# 2.net
KiCad netlist of a schematic drawn in Altium Designer
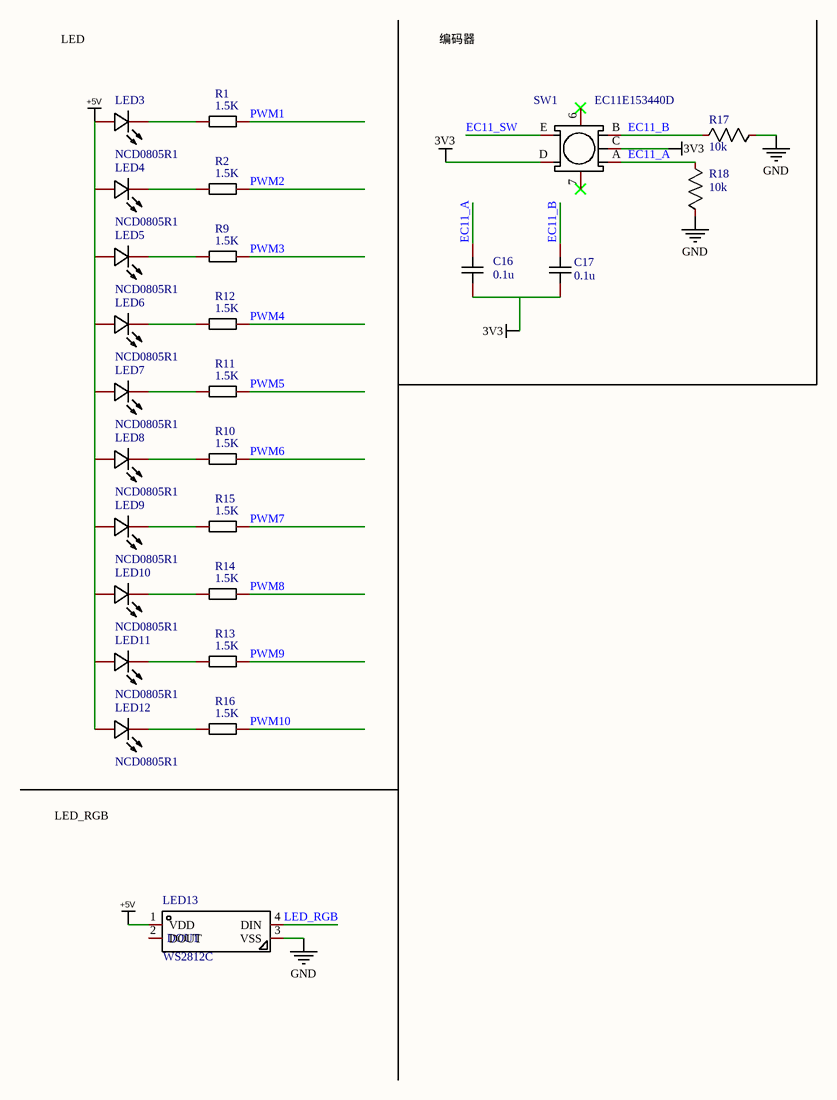
[diagram p0: 2_外围电路.schdoc]

(export (version "E")
  (design (tool "Eeschema 10.0.6"))
  (components
    (comp (ref "C16")
      (value "0.1u")
      (fields (field (name "NAME") "0.1u"))
      (libsource (lib "altium-import") (part "root_1_0.1u_"))
    )
    (comp (ref "C17")
      (value "0.1u")
      (fields (field (name "NAME") "0.1u"))
      (libsource (lib "altium-import") (part "root_1_0.1u_"))
    )
    (comp (ref "LED3")
      (value "NCD0805R1")
      (description "发光颜色:红灯;")
      (fields (field (name "NAME") "NCD0805R1") (field (name "MANUFACTURER") "国星光电"))
      (libsource (lib "altium-import") (part "root_2_NCD0805R1_"))
    )
    (comp (ref "LED4")
      (value "NCD0805R1")
      (description "发光颜色:红灯;")
      (fields (field (name "NAME") "NCD0805R1") (field (name "MANUFACTURER") "国星光电"))
      (libsource (lib "altium-import") (part "root_2_NCD0805R1_"))
    )
    (comp (ref "LED5")
      (value "NCD0805R1")
      (description "发光颜色:红灯;")
      (fields (field (name "NAME") "NCD0805R1") (field (name "MANUFACTURER") "国星光电"))
      (libsource (lib "altium-import") (part "root_2_NCD0805R1_"))
    )
    (comp (ref "LED6")
      (value "NCD0805R1")
      (description "发光颜色:红灯;")
      (fields (field (name "NAME") "NCD0805R1") (field (name "MANUFACTURER") "国星光电"))
      (libsource (lib "altium-import") (part "root_2_NCD0805R1_"))
    )
    (comp (ref "LED7")
      (value "NCD0805R1")
      (description "发光颜色:红灯;")
      (fields (field (name "NAME") "NCD0805R1") (field (name "MANUFACTURER") "国星光电"))
      (libsource (lib "altium-import") (part "root_2_NCD0805R1_"))
    )
    (comp (ref "LED8")
      (value "NCD0805R1")
      (description "发光颜色:红灯;")
      (fields (field (name "NAME") "NCD0805R1") (field (name "MANUFACTURER") "国星光电"))
      (libsource (lib "altium-import") (part "root_2_NCD0805R1_"))
    )
    (comp (ref "LED9")
      (value "NCD0805R1")
      (description "发光颜色:红灯;")
      (fields (field (name "NAME") "NCD0805R1") (field (name "MANUFACTURER") "国星光电"))
      (libsource (lib "altium-import") (part "root_2_NCD0805R1_"))
    )
    (comp (ref "LED10")
      (value "NCD0805R1")
      (description "发光颜色:红灯;")
      (fields (field (name "NAME") "NCD0805R1") (field (name "MANUFACTURER") "国星光电"))
      (libsource (lib "altium-import") (part "root_2_NCD0805R1_"))
    )
    (comp (ref "LED11")
      (value "NCD0805R1")
      (description "发光颜色:红灯;")
      (fields (field (name "NAME") "NCD0805R1") (field (name "MANUFACTURER") "国星光电"))
      (libsource (lib "altium-import") (part "root_2_NCD0805R1_"))
    )
    (comp (ref "LED12")
      (value "NCD0805R1")
      (description "发光颜色:红灯;")
      (fields (field (name "NAME") "NCD0805R1") (field (name "MANUFACTURER") "国星光电"))
      (libsource (lib "altium-import") (part "root_2_NCD0805R1_"))
    )
    (comp (ref "LED13")
      (value "WS2812C")
      (description "发光颜色:RGB三色;")
      (fields
        (field (name "NAME") "WS2812C")
        (field (name "MANUFACTURER") "worldsemi")
        (field (name "NAME_1") "DOUT")
      )
      (libsource (lib "altium-import") (part "root_0_WS2812C_"))
    )
    (comp (ref "R1")
      (value "1.5K")
      (fields
        (field (name "NAME") "1.5K")
        (field (name "MANUFACTURER") "YAGEO(国巨)")
        (field (name "MANUFACTURER PART") "AC0805FR-071K5L")
      )
      (libsource (lib "altium-import") (part "root_0_AC0805FR-071K5L_"))
    )
    (comp (ref "R2")
      (value "1.5K")
      (fields
        (field (name "NAME") "1.5K")
        (field (name "MANUFACTURER") "YAGEO(国巨)")
        (field (name "MANUFACTURER PART") "AC0805FR-071K5L")
      )
      (libsource (lib "altium-import") (part "root_0_AC0805FR-071K5L_"))
    )
    (comp (ref "R9")
      (value "1.5K")
      (fields
        (field (name "NAME") "1.5K")
        (field (name "MANUFACTURER") "YAGEO(国巨)")
        (field (name "MANUFACTURER PART") "AC0805FR-071K5L")
      )
      (libsource (lib "altium-import") (part "root_0_AC0805FR-071K5L_"))
    )
    (comp (ref "R10")
      (value "1.5K")
      (fields
        (field (name "NAME") "1.5K")
        (field (name "MANUFACTURER") "YAGEO(国巨)")
        (field (name "MANUFACTURER PART") "AC0805FR-071K5L")
      )
      (libsource (lib "altium-import") (part "root_0_AC0805FR-071K5L_"))
    )
    (comp (ref "R11")
      (value "1.5K")
      (fields
        (field (name "NAME") "1.5K")
        (field (name "MANUFACTURER") "YAGEO(国巨)")
        (field (name "MANUFACTURER PART") "AC0805FR-071K5L")
      )
      (libsource (lib "altium-import") (part "root_0_AC0805FR-071K5L_"))
    )
    (comp (ref "R12")
      (value "1.5K")
      (fields
        (field (name "NAME") "1.5K")
        (field (name "MANUFACTURER") "YAGEO(国巨)")
        (field (name "MANUFACTURER PART") "AC0805FR-071K5L")
      )
      (libsource (lib "altium-import") (part "root_0_AC0805FR-071K5L_"))
    )
    (comp (ref "R13")
      (value "1.5K")
      (fields
        (field (name "NAME") "1.5K")
        (field (name "MANUFACTURER") "YAGEO(国巨)")
        (field (name "MANUFACTURER PART") "AC0805FR-071K5L")
      )
      (libsource (lib "altium-import") (part "root_0_AC0805FR-071K5L_"))
    )
    (comp (ref "R14")
      (value "1.5K")
      (fields
        (field (name "NAME") "1.5K")
        (field (name "MANUFACTURER") "YAGEO(国巨)")
        (field (name "MANUFACTURER PART") "AC0805FR-071K5L")
      )
      (libsource (lib "altium-import") (part "root_0_AC0805FR-071K5L_"))
    )
    (comp (ref "R15")
      (value "1.5K")
      (fields
        (field (name "NAME") "1.5K")
        (field (name "MANUFACTURER") "YAGEO(国巨)")
        (field (name "MANUFACTURER PART") "AC0805FR-071K5L")
      )
      (libsource (lib "altium-import") (part "root_0_AC0805FR-071K5L_"))
    )
    (comp (ref "R16")
      (value "1.5K")
      (fields
        (field (name "NAME") "1.5K")
        (field (name "MANUFACTURER") "YAGEO(国巨)")
        (field (name "MANUFACTURER PART") "AC0805FR-071K5L")
      )
      (libsource (lib "altium-import") (part "root_0_AC0805FR-071K5L_"))
    )
    (comp (ref "R17")
      (value "10k")
      (fields (field (name "NAME") "10k"))
      (libsource (lib "altium-import") (part "root_2_10k_"))
    )
    (comp (ref "R18")
      (value "10k")
      (fields (field (name "NAME") "10k"))
      (libsource (lib "altium-import") (part "root_3_10k_"))
    )
    (comp (ref "SW1")
      (value "EC11E153440D")
      (fields (field (name "NAME") "EC11E153440D") (field (name "MANUFACTURER") "ALPSALPINE(阿尔卑斯阿尔派)"))
      (libsource (lib "altium-import") (part "root_1_EC11E153440D_"))
    )
  )
  (nets
    (net (code "1") (name "+5V") (class "Default")
      (node (ref "LED10") (pin "2") (pinfunction "+_2") (pintype "passive"))
      (node (ref "LED11") (pin "2") (pinfunction "+_2") (pintype "passive"))
      (node (ref "LED12") (pin "2") (pinfunction "+_2") (pintype "passive"))
      (node (ref "LED13") (pin "1") (pinfunction "VDD_1") (pintype "passive"))
      (node (ref "LED3") (pin "2") (pinfunction "+_2") (pintype "passive"))
      (node (ref "LED4") (pin "2") (pinfunction "+_2") (pintype "passive"))
      (node (ref "LED5") (pin "2") (pinfunction "+_2") (pintype "passive"))
      (node (ref "LED6") (pin "2") (pinfunction "+_2") (pintype "passive"))
      (node (ref "LED7") (pin "2") (pinfunction "+_2") (pintype "passive"))
      (node (ref "LED8") (pin "2") (pinfunction "+_2") (pintype "passive"))
      (node (ref "LED9") (pin "2") (pinfunction "+_2") (pintype "passive"))
    )
    (net (code "2") (name "/EC11_A") (class "Default")
      (node (ref "C16") (pin "2") (pinfunction "2_2") (pintype "passive"))
      (node (ref "R18") (pin "1") (pinfunction "1_1") (pintype "passive"))
      (node (ref "SW1") (pin "A") (pinfunction "A_A") (pintype "passive"))
    )
    (net (code "3") (name "/EC11_B") (class "Default")
      (node (ref "C17") (pin "2") (pinfunction "2_2") (pintype "passive"))
      (node (ref "R17") (pin "2") (pinfunction "2_2") (pintype "passive"))
      (node (ref "SW1") (pin "B") (pinfunction "B_B") (pintype "passive"))
    )
    (net (code "4") (name "/EC11_SW") (class "Default")
      (node (ref "SW1") (pin "E") (pinfunction "E_E") (pintype "passive"))
    )
    (net (code "5") (name "/LED_RGB") (class "Default")
      (node (ref "LED13") (pin "4") (pinfunction "DIN_4") (pintype "passive"))
    )
    (net (code "6") (name "/PWM1") (class "Default")
      (node (ref "R1") (pin "2") (pinfunction "2_2") (pintype "passive"))
    )
    (net (code "7") (name "/PWM2") (class "Default")
      (node (ref "R2") (pin "2") (pinfunction "2_2") (pintype "passive"))
    )
    (net (code "8") (name "/PWM3") (class "Default")
      (node (ref "R9") (pin "2") (pinfunction "2_2") (pintype "passive"))
    )
    (net (code "9") (name "/PWM4") (class "Default")
      (node (ref "R12") (pin "2") (pinfunction "2_2") (pintype "passive"))
    )
    (net (code "10") (name "/PWM5") (class "Default")
      (node (ref "R11") (pin "2") (pinfunction "2_2") (pintype "passive"))
    )
    (net (code "11") (name "/PWM6") (class "Default")
      (node (ref "R10") (pin "2") (pinfunction "2_2") (pintype "passive"))
    )
    (net (code "12") (name "/PWM7") (class "Default")
      (node (ref "R15") (pin "2") (pinfunction "2_2") (pintype "passive"))
    )
    (net (code "13") (name "/PWM8") (class "Default")
      (node (ref "R14") (pin "2") (pinfunction "2_2") (pintype "passive"))
    )
    (net (code "14") (name "/PWM9") (class "Default")
      (node (ref "R13") (pin "2") (pinfunction "2_2") (pintype "passive"))
    )
    (net (code "15") (name "/PWM10") (class "Default")
      (node (ref "R16") (pin "2") (pinfunction "2_2") (pintype "passive"))
    )
    (net (code "16") (name "3V3") (class "Default")
      (node (ref "C16") (pin "1") (pinfunction "1_1") (pintype "passive"))
      (node (ref "C17") (pin "1") (pinfunction "1_1") (pintype "passive"))
      (node (ref "SW1") (pin "C") (pinfunction "C_C") (pintype "passive"))
      (node (ref "SW1") (pin "D") (pinfunction "D_D") (pintype "passive"))
    )
    (net (code "17") (name "GND") (class "Default")
      (node (ref "LED13") (pin "3") (pinfunction "VSS_3") (pintype "passive"))
      (node (ref "R17") (pin "1") (pinfunction "1_1") (pintype "passive"))
      (node (ref "R18") (pin "2") (pinfunction "2_2") (pintype "passive"))
    )
    (net (code "18") (name "Net-(LED3--)") (class "Default")
      (node (ref "LED3") (pin "1") (pinfunction "-_1") (pintype "passive"))
      (node (ref "R1") (pin "1") (pinfunction "1_1") (pintype "passive"))
    )
    (net (code "19") (name "Net-(LED4--)") (class "Default")
      (node (ref "LED4") (pin "1") (pinfunction "-_1") (pintype "passive"))
      (node (ref "R2") (pin "1") (pinfunction "1_1") (pintype "passive"))
    )
    (net (code "20") (name "Net-(LED5--)") (class "Default")
      (node (ref "LED5") (pin "1") (pinfunction "-_1") (pintype "passive"))
      (node (ref "R9") (pin "1") (pinfunction "1_1") (pintype "passive"))
    )
    (net (code "21") (name "Net-(LED6--)") (class "Default")
      (node (ref "LED6") (pin "1") (pinfunction "-_1") (pintype "passive"))
      (node (ref "R12") (pin "1") (pinfunction "1_1") (pintype "passive"))
    )
    (net (code "22") (name "Net-(LED7--)") (class "Default")
      (node (ref "LED7") (pin "1") (pinfunction "-_1") (pintype "passive"))
      (node (ref "R11") (pin "1") (pinfunction "1_1") (pintype "passive"))
    )
    (net (code "23") (name "Net-(LED8--)") (class "Default")
      (node (ref "LED8") (pin "1") (pinfunction "-_1") (pintype "passive"))
      (node (ref "R10") (pin "1") (pinfunction "1_1") (pintype "passive"))
    )
    (net (code "24") (name "Net-(LED9--)") (class "Default")
      (node (ref "LED9") (pin "1") (pinfunction "-_1") (pintype "passive"))
      (node (ref "R15") (pin "1") (pinfunction "1_1") (pintype "passive"))
    )
    (net (code "25") (name "Net-(LED10--)") (class "Default")
      (node (ref "LED10") (pin "1") (pinfunction "-_1") (pintype "passive"))
      (node (ref "R14") (pin "1") (pinfunction "1_1") (pintype "passive"))
    )
    (net (code "26") (name "Net-(LED11--)") (class "Default")
      (node (ref "LED11") (pin "1") (pinfunction "-_1") (pintype "passive"))
      (node (ref "R13") (pin "1") (pinfunction "1_1") (pintype "passive"))
    )
    (net (code "27") (name "Net-(LED12--)") (class "Default")
      (node (ref "LED12") (pin "1") (pinfunction "-_1") (pintype "passive"))
      (node (ref "R16") (pin "1") (pinfunction "1_1") (pintype "passive"))
    )
    (net (code "28") (name "unconnected-(LED13-DOUT-Pad2)") (class "Default")
      (node (ref "LED13") (pin "2") (pinfunction "DOUT_2") (pintype "passive"))
    )
    (net (code "29") (name "unconnected-(SW1-Pad6)") (class "Default")
      (node (ref "SW1") (pin "6") (pinfunction "6_6") (pintype "passive+no_connect"))
    )
    (net (code "30") (name "unconnected-(SW1-Pad7)") (class "Default")
      (node (ref "SW1") (pin "7") (pinfunction "7_7") (pintype "passive+no_connect"))
    )
  )
)
